# Power.net
KiCad netlist of a schematic drawn in Altium Designer
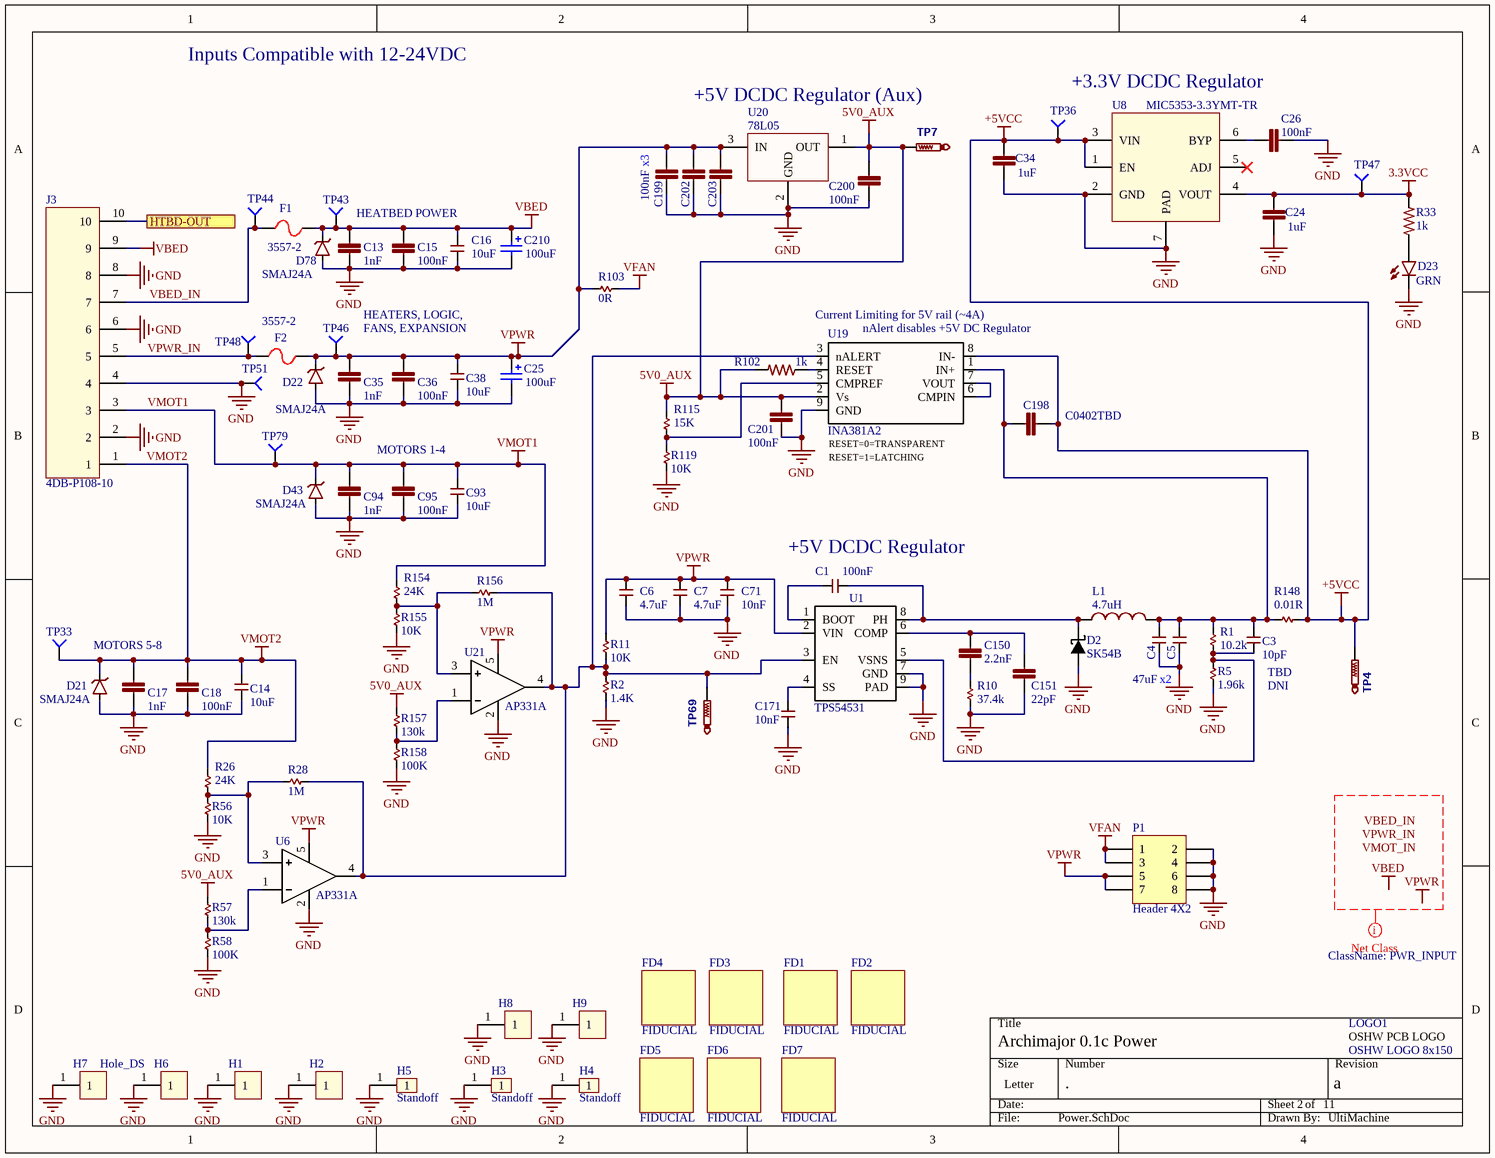
[diagram p0: Power.SchDoc]

(export (version "E")
  (design (tool "Eeschema 10.0.6"))
  (components
    (comp (ref "C1")
      (value "100nF")
      (footprint "C0603")
      (description "CAP CER 0603 100nF 50V 10% X7R")
      (fields (field (name "MANUFACTURER") "Kemet") (field (name "TOLERANCE") "+/- 10%"))
      (libsource (lib "Capacitors") (part "100nF 0603 50V X7R"))
    )
    (comp (ref "C3")
      (value "10pF")
      (footprint "C0402")
      (description "CAP CER 0402 TBD")
      (fields
        (field (name "PART DESCRIPTION") "TBD")
        (field (name "MANUFACTURER") "TBD")
        (field (name "DNI") "DNI")
      )
      (libsource (lib "Capacitors") (part "C0402_TBD"))
    )
    (comp (ref "C4")
      (value "47uF")
      (footprint "C1210")
      (description "CAP CER 47UF 10V X5R 1210")
      (fields (field (name "MANUFACTURER") "Murata") (field (name "TOLERANCE") "10%"))
      (libsource (lib "Capacitors") (part "47uF 1210 10V X5R"))
    )
    (comp (ref "C5")
      (value "47uF")
      (footprint "C1210")
      (description "CAP CER 47UF 10V X5R 1210")
      (fields (field (name "MANUFACTURER") "Murata") (field (name "TOLERANCE") "10%"))
      (libsource (lib "Capacitors") (part "47uF 1210 10V X5R"))
    )
    (comp (ref "C6")
      (value "4.7uF")
      (footprint "C1210")
      (description "CAP CER 4.7UF 50V X7R 1210")
      (fields (field (name "MANUFACTURER") "Murata") (field (name "PART") "4.7uF 1210 50V X7R"))
      (libsource (lib "Capacitors") (part "4.7uF 1210 50V X7R"))
    )
    (comp (ref "C7")
      (value "4.7uF")
      (footprint "C1210")
      (description "CAP CER 4.7UF 50V X7R 1210")
      (fields (field (name "MANUFACTURER") "Murata") (field (name "PART") "4.7uF 1210 50V X7R"))
      (libsource (lib "Capacitors") (part "4.7uF 1210 50V X7R"))
    )
    (comp (ref "C13")
      (value "1nF")
      (footprint "C0402")
      (description "1000pF 50V Ceramic Capacitor X7R 0402 (1005 Metric) 0.039\" L x 0.020\" W (1.00mm x 0.50mm)")
      (fields (field (name "MANUFACTURER") "Murata") (field (name "PART") "1nF 50V X7R 0402"))
      (libsource (lib "3Delight") (part "CAP 1nF 50V 0402 X7R"))
    )
    (comp (ref "C14")
      (value "10uF")
      (footprint "C1206")
      (description "CAP CER 10UF 50V 10% X5R 1206")
      (fields (field (name "MANUFACTURER") "Murata") (field (name "PART") "CAP CER 10UF 50V X5R 1206"))
      (libsource (lib "Capacitors") (part "10uF 1206 50V X5R"))
    )
    (comp (ref "C15")
      (value "100nF")
      (footprint "C0603")
      (description "CAP CER 0603 100nF 50V 10% X7R")
      (fields (field (name "MANUFACTURER") "Kemet") (field (name "PART") "100nF 50V X7R 0603"))
      (libsource (lib "3Delight") (part "C0603C104K5RACTU"))
    )
    (comp (ref "C16")
      (value "10uF")
      (footprint "C1206")
      (description "CAP CER 10UF 50V 10% X5R 1206")
      (fields (field (name "MANUFACTURER") "Murata") (field (name "PART") "CAP CER 10UF 50V X5R 1206"))
      (libsource (lib "Capacitors") (part "10uF 1206 50V X5R"))
    )
    (comp (ref "C17")
      (value "1nF")
      (footprint "C0402")
      (description "1000pF 50V Ceramic Capacitor X7R 0402 (1005 Metric) 0.039\" L x 0.020\" W (1.00mm x 0.50mm)")
      (fields (field (name "MANUFACTURER") "Murata") (field (name "PART") "1nF 50V X7R 0402"))
      (libsource (lib "3Delight") (part "CAP 1nF 50V 0402 X7R"))
    )
    (comp (ref "C18")
      (value "100nF")
      (footprint "C0603")
      (description "CAP CER 0603 100nF 50V 10% X7R")
      (fields (field (name "MANUFACTURER") "Kemet") (field (name "PART") "100nF 50V X7R 0603"))
      (libsource (lib "3Delight") (part "C0603C104K5RACTU"))
    )
    (comp (ref "C24")
      (value "1uF")
      (footprint "C0402")
      (description "CAP CER 0402 1uF 6.3V 10% X5R")
      (fields (field (name "MANUFACTURER") "Murata") (field (name "PART") "1uF 6.3V X5R 0402"))
      (libsource (lib "3Delight") (part "GRM155R60J105KE19D"))
    )
    (comp (ref "C25")
      (value "100uF")
      (footprint "CAP-ELEC-063063077")
      (description "CAP ALUM 100UF 35V 20% SMD")
      (fields (field (name "MANUFACTURER") "Nichicon") (field (name "PART") "100uF 35V SMD Al-El"))
      (libsource (lib "3Delight") (part "UWT1V101MCL1GS"))
    )
    (comp (ref "C26")
      (value "100nF")
      (footprint "C0402")
      (description "CAP CER 0402 100nF 16V 10% X7R")
      (fields (field (name "MANUFACTURER") "Murata") (field (name "PART") "0.1uF 16V X7R 0402"))
      (libsource (lib "") (part "GRM155R71C104KA88D_1"))
    )
    (comp (ref "C34")
      (value "1uF")
      (footprint "C0402")
      (description "CAP CER 0402 1uF 6.3V 10% X5R")
      (fields (field (name "MANUFACTURER") "Murata") (field (name "PART") "1uF 6.3V X5R 0402"))
      (libsource (lib "3Delight") (part "GRM155R60J105KE19D"))
    )
    (comp (ref "C35")
      (value "1nF")
      (footprint "C0402")
      (description "1000pF 50V Ceramic Capacitor X7R 0402 (1005 Metric) 0.039\" L x 0.020\" W (1.00mm x 0.50mm)")
      (fields (field (name "MANUFACTURER") "Murata") (field (name "PART") "1nF 50V X7R 0402"))
      (libsource (lib "3Delight") (part "CAP 1nF 50V 0402 X7R"))
    )
    (comp (ref "C36")
      (value "100nF")
      (footprint "C0603")
      (description "CAP CER 0603 100nF 50V 10% X7R")
      (fields (field (name "MANUFACTURER") "Kemet") (field (name "PART") "100nF 50V X7R 0603"))
      (libsource (lib "3Delight") (part "C0603C104K5RACTU"))
    )
    (comp (ref "C38")
      (value "10uF")
      (footprint "C1206")
      (description "CAP CER 10UF 50V 10% X5R 1206")
      (fields (field (name "MANUFACTURER") "Murata") (field (name "PART") "CAP CER 10UF 50V X5R 1206"))
      (libsource (lib "Capacitors") (part "10uF 1206 50V X5R"))
    )
    (comp (ref "C71")
      (value "10nF")
      (footprint "C0402")
      (description "CAP CER 10nF 50V X7R 0402")
      (fields (field (name "TOLERANCE") "5%") (field (name "MANUFACTURER") "Murata"))
      (libsource (lib "Capacitors") (part "10nF 0402 50V X7R"))
    )
    (comp (ref "C93")
      (value "10uF")
      (footprint "C1206")
      (description "CAP CER 10UF 50V 10% X5R 1206")
      (fields (field (name "MANUFACTURER") "Murata") (field (name "PART") "CAP CER 10UF 50V X5R 1206"))
      (libsource (lib "Capacitors") (part "10uF 1206 50V X5R"))
    )
    (comp (ref "C94")
      (value "1nF")
      (footprint "C0402")
      (description "1000pF 50V Ceramic Capacitor X7R 0402 (1005 Metric) 0.039\" L x 0.020\" W (1.00mm x 0.50mm)")
      (fields (field (name "MANUFACTURER") "Murata") (field (name "PART") "1nF 50V X7R 0402"))
      (libsource (lib "3Delight") (part "CAP 1nF 50V 0402 X7R"))
    )
    (comp (ref "C95")
      (value "100nF")
      (footprint "C0603")
      (description "CAP CER 0603 100nF 50V 10% X7R")
      (fields (field (name "MANUFACTURER") "Kemet") (field (name "PART") "100nF 50V X7R 0603"))
      (libsource (lib "3Delight") (part "C0603C104K5RACTU"))
    )
    (comp (ref "C150")
      (value "2.2nF")
      (footprint "C0402")
      (description "CAP CER 0402 2.2nF 25V C0G")
      (fields (field (name "MANUFACTURER") "Kemet") (field (name "PART") "2.2nF 25V C0G 0402"))
      (libsource (lib "Capacitors") (part "2.2nF 25V C0G 0402"))
    )
    (comp (ref "C151")
      (value "22pF")
      (footprint "C0402")
      (description "CAP CER 0402 22pF 50V 5% C0G")
      (fields (field (name "MANUFACTURER") "AVX") (field (name "PART") "22pF 50V"))
      (libsource (lib "Capacitors") (part "22pF 0402 50V C0G"))
    )
    (comp (ref "C171")
      (value "10nF")
      (footprint "C0402")
      (description "CAP CER 10nF 50V X7R 0402")
      (fields (field (name "TOLERANCE") "5%") (field (name "MANUFACTURER") "Murata"))
      (libsource (lib "Capacitors") (part "10nF 0402 50V X7R"))
    )
    (comp (ref "C198")
      (value "C0402TBD")
      (footprint "C0402")
      (description "Capacitor Non Polarized")
      (libsource (lib "Capacitors") (part "C0402TBD"))
    )
    (comp (ref "C199")
      (value "100nF")
      (footprint "C0603")
      (description "CAP CER 0603 100nF 50V 10% X7R")
      (fields (field (name "MANUFACTURER") "Kemet") (field (name "PART") "100nF 50V X7R 0603"))
      (libsource (lib "3Delight") (part "C0603C104K5RACTU"))
    )
    (comp (ref "C200")
      (value "100nF")
      (footprint "C0402")
      (description "CAP CER 0402 100nF 16V 10% X7R")
      (fields (field (name "MANUFACTURER") "Murata") (field (name "PART") "0.1uF 16V X7R 0402"))
      (libsource (lib "3Delight") (part "GRM155R71C104KA88D"))
    )
    (comp (ref "C201")
      (value "100nF")
      (footprint "C0402")
      (description "CAP CER 0402 100nF 16V 10% X7R")
      (fields (field (name "MANUFACTURER") "Murata") (field (name "PART") "0.1uF 16V X7R 0402"))
      (libsource (lib "3Delight") (part "GRM155R71C104KA88D"))
    )
    (comp (ref "C202")
      (value "100nF")
      (footprint "C0603")
      (description "CAP CER 0603 100nF 50V 10% X7R")
      (fields (field (name "MANUFACTURER") "Kemet") (field (name "PART") "100nF 50V X7R 0603"))
      (libsource (lib "3Delight") (part "C0603C104K5RACTU"))
    )
    (comp (ref "C203")
      (value "100nF")
      (footprint "C0603")
      (description "CAP CER 0603 100nF 50V 10% X7R")
      (fields (field (name "MANUFACTURER") "Kemet") (field (name "PART") "100nF 50V X7R 0603"))
      (libsource (lib "3Delight") (part "C0603C104K5RACTU"))
    )
    (comp (ref "C210")
      (value "100uF")
      (footprint "CAP-ELEC-063063077")
      (description "CAP ALUM 100UF 35V 20% SMD")
      (fields (field (name "MANUFACTURER") "Nichicon") (field (name "PART") "100uF 35V SMD Al-El"))
      (libsource (lib "3Delight") (part "UWT1V101MCL1GS"))
    )
    (comp (ref "D2")
      (value "SK54B")
      (footprint "SMB_DO-214AA_LRG")
      (description "DIODE SCHOTTKY 40V 5A SMB_DO214AA")
      (fields (field (name "MANUFACTURER") "MCC") (field (name "VOLTAGE") "40Vrb"))
      (libsource (lib "Diodes") (part "SK54B"))
    )
    (comp (ref "D21")
      (value "SMAJ24A")
      (footprint "SMA-SM")
      (description "TVS DIODE 24V 38.9V SMA")
      (fields (field (name "MANUFACTURER") "Bourns Inc"))
      (libsource (lib "Diodes") (part "SMAJ24A"))
    )
    (comp (ref "D22")
      (value "SMAJ24A")
      (footprint "SMA-SM")
      (description "TVS DIODE 24V 38.9V SMA")
      (fields (field (name "MANUFACTURER") "Bourns Inc"))
      (libsource (lib "Diodes") (part "SMAJ24A"))
    )
    (comp (ref "D23")
      (value "GRN")
      (footprint "LED2012120")
      (description "LED 0805 Green")
      (fields (field (name "MANUFACTURER") "Dialight") (field (name "PART") "LED GREEN CLEAR 0805 SMD"))
      (libsource (lib "LEDs") (part "5988170107F"))
    )
    (comp (ref "D43")
      (value "SMAJ24A")
      (footprint "SMA-SM")
      (description "TVS DIODE 24V 38.9V SMA")
      (fields (field (name "MANUFACTURER") "Bourns Inc"))
      (libsource (lib "Diodes") (part "SMAJ24A"))
    )
    (comp (ref "D78")
      (value "SMAJ24A")
      (footprint "SMA-SM")
      (description "TVS DIODE 24V 38.9V SMA")
      (fields (field (name "MANUFACTURER") "Bourns Inc"))
      (libsource (lib "Diodes") (part "SMAJ24A"))
    )
    (comp (ref "F1")
      (value "3557-2")
      (footprint "3557")
      (description "FUSE PTH ATO")
      (fields (field (name "MANUFACTURER") "Keystone") (field (name "PART") "Fuse Holder"))
      (libsource (lib "3Delight") (part "3557-2"))
    )
    (comp (ref "F2")
      (value "3557-2")
      (footprint "3557")
      (description "FUSE PTH ATO")
      (fields (field (name "MANUFACTURER") "Keystone") (field (name "PART") "Fuse Holder"))
      (libsource (lib "3Delight") (part "3557-2"))
    )
    (comp (ref "FD1")
      (value "FIDUCIAL")
      (footprint "FIDUCIAL-1X2")
      (libsource (lib "3Delight") (part "FIDUCIAL"))
    )
    (comp (ref "FD2")
      (value "FIDUCIAL")
      (footprint "FIDUCIAL-1X2")
      (libsource (lib "3Delight") (part "FIDUCIAL"))
    )
    (comp (ref "FD3")
      (value "FIDUCIAL")
      (footprint "FIDUCIAL-1X2")
      (libsource (lib "3Delight") (part "FIDUCIAL"))
    )
    (comp (ref "FD4")
      (value "FIDUCIAL")
      (footprint "FIDUCIAL-1X2")
      (libsource (lib "3Delight") (part "FIDUCIAL"))
    )
    (comp (ref "FD5")
      (value "FIDUCIAL")
      (footprint "FIDUCIAL-1X2")
      (libsource (lib "3Delight") (part "FIDUCIAL"))
    )
    (comp (ref "FD6")
      (value "FIDUCIAL")
      (footprint "FIDUCIAL-1X2")
      (libsource (lib "3Delight") (part "FIDUCIAL"))
    )
    (comp (ref "FD7")
      (value "FIDUCIAL")
      (footprint "FIDUCIAL-1X2")
      (libsource (lib "3Delight") (part "FIDUCIAL"))
    )
    (comp (ref "H1")
      (value "Hole_DS")
      (footprint "Wave_hole_3x7-doubleSided")
      (libsource (lib "Archim_0.4") (part "Hole_DS"))
    )
    (comp (ref "H2")
      (value "Hole_DS")
      (footprint "Wave_hole_3x7-doubleSided")
      (libsource (lib "Archim_0.4") (part "Hole_DS"))
    )
    (comp (ref "H3")
      (value "Standoff")
      (footprint "Standoff3mmTopConn")
      (description "Mechanical - Top connect")
      (libsource (lib "3Delight") (part "Standoff3TopConn"))
    )
    (comp (ref "H4")
      (value "Standoff")
      (footprint "Standoff3mmTopConn")
      (description "Mechanical - Top connect")
      (libsource (lib "3Delight") (part "Standoff3TopConn"))
    )
    (comp (ref "H5")
      (value "Standoff")
      (footprint "Standoff3mmTopConn")
      (description "Mechanical - Top connect")
      (libsource (lib "3Delight") (part "Standoff3TopConn"))
    )
    (comp (ref "H6")
      (value "Hole_DS")
      (footprint "Wave_hole_3x7-doubleSided")
      (libsource (lib "Archim_0.4") (part "Hole_DS"))
    )
    (comp (ref "H7")
      (value "Hole_DS")
      (footprint "Wave_hole_3x7-doubleSided")
      (libsource (lib "Archim_0.4") (part "Hole_DS"))
    )
    (comp (ref "H8")
      (value "Hole_DS")
      (footprint "Wave_hole_3x7-doubleSided")
      (libsource (lib "Archim_0.4") (part "Hole_DS"))
    )
    (comp (ref "H9")
      (value "Hole_DS")
      (footprint "Wave_hole_3x7-doubleSided")
      (libsource (lib "Archim_0.4") (part "Hole_DS"))
    )
    (comp (ref "J3")
      (value "4DB-P108-10")
      (footprint "CON-Barrier-10-8.26mm")
      (description "CONN BARRIER STRIP 10CIRC 0.325\"")
      (fields (field (name "MANUFACTURER") "TE") (field (name "TOLERANCE") "NA"))
      (libsource (lib "Connectors") (part "10 Pos barrier"))
    )
    (comp (ref "L1")
      (value "4.7uH")
      (footprint "IND_10X10")
      (description "FIXED IND 4.7UH 10A 15.5 MOHM")
      (fields (field (name "MANUFACTURER") "Bourns") (field (name "PART") "4.7uH 10A"))
      (libsource (lib "Inductors") (part "4.7uH 10A"))
    )
    (comp (ref "LOGO1")
      (value "OSHW LOGO 8x150")
      (footprint "OSHW_8X150_NOTEXT")
      (libsource (lib "MISC") (part "OSHW LOGO 8x150"))
    )
    (comp (ref "P1")
      (value "Header 4X2")
      (footprint "HDR2X4")
      (description "Header, 4-Pin, Dual row")
      (fields (field (name "MANUFACTURER") "Multicomp") (field (name "PART") "CONN 8Pin 2Row 0.1\""))
      (libsource (lib "Miscellaneous Connectors") (part "Header 4X2"))
    )
    (comp (ref "R1")
      (value "10.2k")
      (footprint "R0402")
      (description "RES SMD 10.2K OHM 1% 1/16W 0402")
      (fields (field (name "MANUFACTURER") "Yageo") (field (name "PART") "10.2k 1% 0402"))
      (libsource (lib "Resistors") (part "10.2k 1% 0402"))
    )
    (comp (ref "R2")
      (value "1.4K")
      (footprint "R0402")
      (description "RES SMD 1.4K OHM 1% 1/16W 0402")
      (fields (field (name "MANUFACTURER") "Stackpole") (field (name "TOLERANCE") "+/- 1%"))
      (libsource (lib "Resistors") (part "1.4k 1% 0402"))
    )
    (comp (ref "R5")
      (value "1.96k")
      (footprint "R0402")
      (description "RES SMD 1.96K OHM 1% 1/16W 0402")
      (fields (field (name "MANUFACTURER") "Yageo") (field (name "PART") "1.96k 1% 0402"))
      (libsource (lib "Resistors") (part "1.96k 1% 0402"))
    )
    (comp (ref "R10")
      (value "37.4k")
      (footprint "R0402")
      (description "RES SMD 37.4K OHM 1% 1/16W 0402")
      (fields (field (name "MANUFACTURER") "Yageo") (field (name "TOLERANCE") "1%"))
      (libsource (lib "Resistors") (part "37.4K 1% 0402"))
    )
    (comp (ref "R11")
      (value "10K")
      (footprint "R0402")
      (description "RES SMD 10K OHM 1% 1/16W 0402")
      (fields (field (name "MANUFACTURER") "Yageo") (field (name "PART") "10k 1% 0402"))
      (libsource (lib "Resistors") (part "10k 1% 0402"))
    )
    (comp (ref "R26")
      (value "24K")
      (footprint "R0402")
      (description "RES SMD 24K OHM 1% 1/16W 0402")
      (fields (field (name "MANUFACTURER") "Visha Dale") (field (name "TOLERANCE") "+/- 1%"))
      (libsource (lib "Resistors") (part "24k 1% 0402"))
    )
    (comp (ref "R28")
      (value "1M")
      (footprint "Passives:R0402")
      (description "RES 0402 1M 100mW 5%")
      (fields (field (name "MANUFACTURER") "Panasonic") (field (name "PART") "1M 5% 0402"))
      (libsource (lib "Resistors") (part "1M 5% 0402"))
    )
    (comp (ref "R33")
      (value "1k")
      (footprint "R0402")
      (description "RES 0402 1k 63mW 1%")
      (fields (field (name "MANUFACTURER") "Yageo") (field (name "PART") "1k 1% 0402"))
      (libsource (lib "3Delight") (part "RK73H1ETTP1001F"))
    )
    (comp (ref "R56")
      (value "10K")
      (footprint "R0402")
      (description "RES SMD 10K OHM 1% 1/16W 0402")
      (fields (field (name "MANUFACTURER") "Yageo") (field (name "PART") "10k 1% 0402"))
      (libsource (lib "Resistors") (part "10k 1% 0402"))
    )
    (comp (ref "R57")
      (value "130k")
      (footprint "Passives:R0402")
      (description "RES SMD 130K OHM 5% 1/16W 0402")
      (fields (field (name "MANUFACTURER") "Yageo") (field (name "PART") "130k 1% 0402"))
      (libsource (lib "Resistors") (part "130k 1% 0402"))
    )
    (comp (ref "R58")
      (value "100K")
      (footprint "Passives:R0402")
      (description "RES SMD 100K OHM 1% 1/16W 0402")
      (fields (field (name "MANUFACTURER") "Samsung") (field (name "PART") "100k 1% 0402"))
      (libsource (lib "Resistors") (part "100k 1% 0402"))
    )
    (comp (ref "R102")
      (value "1k")
      (footprint "R0402")
      (description "RES 0402 1k 63mW 1%")
      (fields (field (name "MANUFACTURER") "Yageo") (field (name "PART") "1k 1% 0402"))
      (libsource (lib "3Delight") (part "RK73H1ETTP1001F"))
    )
    (comp (ref "R103")
      (value "0R")
      (footprint "R0603")
      (description "RES SMD 0.0OHM JUMPER 1/10W 0603")
      (fields (field (name "MANUFACTURER") "Bourns") (field (name "TOLERANCE") "-NA-"))
      (libsource (lib "Resistors") (part "0R 0603"))
    )
    (comp (ref "R115")
      (value "15K")
      (footprint "R0402")
      (description "RES SMD 15K 1% 1/16W 0402")
      (fields (field (name "MANUFACTURER") "Samsung") (field (name "PART") "15K 1% 0402"))
      (libsource (lib "Resistors") (part "15K 1% 0402"))
    )
    (comp (ref "R119")
      (value "10K")
      (footprint "R0402")
      (description "RES SMD 10K OHM 1% 1/16W 0402")
      (fields (field (name "MANUFACTURER") "Yageo") (field (name "PART") "10k 1% 0402"))
      (libsource (lib "Resistors") (part "10k 1% 0402"))
    )
    (comp (ref "R148")
      (value "0.01R")
      (footprint "R0805")
      (description "RES 0.01 OHM 1% 1/2W 0805")
      (fields (field (name "MANUFACTURER") "Susumu") (field (name "PART") "0.01 1% 0.5W 0805"))
      (libsource (lib "Resistors") (part "0.01R 1% 0805"))
    )
    (comp (ref "R154")
      (value "24K")
      (footprint "R0402")
      (description "RES SMD 24K OHM 1% 1/16W 0402")
      (fields (field (name "MANUFACTURER") "Visha Dale") (field (name "TOLERANCE") "+/- 1%"))
      (libsource (lib "Resistors") (part "24k 1% 0402"))
    )
    (comp (ref "R155")
      (value "10K")
      (footprint "R0402")
      (description "RES SMD 10K OHM 1% 1/16W 0402")
      (fields (field (name "MANUFACTURER") "Yageo") (field (name "PART") "10k 1% 0402"))
      (libsource (lib "Resistors") (part "10k 1% 0402"))
    )
    (comp (ref "R156")
      (value "1M")
      (footprint "Passives:R0402")
      (description "RES 0402 1M 100mW 5%")
      (fields (field (name "MANUFACTURER") "Panasonic") (field (name "PART") "1M 5% 0402"))
      (libsource (lib "Resistors") (part "1M 5% 0402"))
    )
    (comp (ref "R157")
      (value "130k")
      (footprint "Passives:R0402")
      (description "RES SMD 130K OHM 5% 1/16W 0402")
      (fields (field (name "MANUFACTURER") "Yageo") (field (name "PART") "130k 1% 0402"))
      (libsource (lib "Resistors") (part "130k 1% 0402"))
    )
    (comp (ref "R158")
      (value "100K")
      (footprint "Passives:R0402")
      (description "RES SMD 100K OHM 1% 1/16W 0402")
      (fields (field (name "MANUFACTURER") "Samsung") (field (name "PART") "100k 1% 0402"))
      (libsource (lib "Resistors") (part "100k 1% 0402"))
    )
    (comp (ref "TP4")
      (value "TestPoint")
      (footprint "TP1-27")
      (description "Test Point")
      (libsource (lib "3Delight") (part "TestPoint"))
    )
    (comp (ref "TP7")
      (value "TestPoint")
      (footprint "TP1-27")
      (description "Test Point")
      (libsource (lib "") (part "TestPoint_1"))
    )
    (comp (ref "TP33")
      (value "TP4")
      (footprint "TP-2")
      (description "Socket")
      (libsource (lib "Archim") (part "Socket"))
    )
    (comp (ref "TP36")
      (value "TP4")
      (footprint "TP-2")
      (description "Socket")
      (libsource (lib "Archim") (part "Socket"))
    )
    (comp (ref "TP43")
      (value "TP4")
      (footprint "TP-2")
      (description "Socket")
      (libsource (lib "Archim") (part "Socket"))
    )
    (comp (ref "TP44")
      (value "TP4")
      (footprint "TP-2")
      (description "Socket")
      (libsource (lib "Archim") (part "Socket"))
    )
    (comp (ref "TP46")
      (value "TP4")
      (footprint "TP-2")
      (description "Socket")
      (libsource (lib "Archim") (part "Socket"))
    )
    (comp (ref "TP47")
      (value "TP4")
      (footprint "TP-2")
      (description "Socket")
      (libsource (lib "Archim") (part "Socket"))
    )
    (comp (ref "TP48")
      (value "TP4")
      (footprint "TP-2")
      (description "Socket")
      (libsource (lib "Archim") (part "Socket"))
    )
    (comp (ref "TP51")
      (value "TP4")
      (footprint "TP-2")
      (description "Socket")
      (libsource (lib "Archim") (part "Socket"))
    )
    (comp (ref "TP69")
      (value "TestPoint")
      (footprint "TP1-27")
      (description "Test Point")
      (libsource (lib "3Delight") (part "TestPoint"))
    )
    (comp (ref "TP79")
      (value "TP4")
      (footprint "TP-2")
      (description "Socket")
      (libsource (lib "Archim") (part "Socket"))
    )
    (comp (ref "U1")
      (value "TPS54531")
      (footprint "SOIC127P600X170_HS-9L")
      (description "IC REG BUCK ADJ 5A 8SOPWRPAD")
      (fields (field (name "MANUFACTURER") "TI"))
      (libsource (lib "ICs-Power") (part "TPS54531"))
    )
    (comp (ref "U6")
      (value "AP331A")
      (footprint "SOT23-5")
      (description "IC QUAD DIFF COMPARATOR 14 -SOIC")
      (fields (field (name "MANUFACTURER") "TEXAS INSTRUMENTS"))
      (libsource (lib "ICs-Analog") (part "AP331A"))
    )
    (comp (ref "U8")
      (value "MIC5353-3.3YMT-TR")
      (footprint "TDFN1616-6LD-PL-1")
      (description "LDO 3.3V 500mA - low ESR Cout")
      (fields (field (name "MANUFACTURER") "Microchip") (field (name "PART") "IC REG LDO 3.3V 0.5A 6TMLF"))
      (libsource (lib "Tigershark3D") (part "MIC5353-3.3YMT-TR"))
    )
    (comp (ref "U19")
      (value "INA381A2")
      (footprint "WSON8_2x2mm")
      (description "IC COMPARATOR BIDIR 8WSON")
      (fields (field (name "MANUFACTURER") "TI") (field (name "TOLERANCE") "-NA-"))
      (libsource (lib "ICs-Analog") (part "INA381_ALT"))
    )
    (comp (ref "U20")
      (value "78L05")
      (footprint "SOT-89-3")
      (description "IC REG LINEAR 5V 100MA SOT89-3")
      (fields (field (name "MANUFACTURER") "ST") (field (name "TOLERANCE") "-NA-"))
      (libsource (lib "ICs-Power") (part "78L05"))
    )
    (comp (ref "U21")
      (value "AP331A")
      (footprint "SOT23-5")
      (description "IC QUAD DIFF COMPARATOR 14 -SOIC")
      (fields (field (name "MANUFACTURER") "TEXAS INSTRUMENTS"))
      (libsource (lib "ICs-Analog") (part "AP331A"))
    )
  )
  (nets
    (net (code "1") (name "+5VCC") (class "Default")
      (node (ref "C198") (pin "1") (pinfunction "1_1") (pintype "passive"))
      (node (ref "C34") (pin "1") (pinfunction "1_1") (pintype "passive"))
      (node (ref "R148") (pin "2") (pinfunction "2_2") (pintype "passive"))
      (node (ref "TP36") (pin "1") (pinfunction "1_1") (pintype "passive"))
      (node (ref "TP4") (pin "TP") (pinfunction "TP_TP") (pintype "passive"))
      (node (ref "U19") (pin "8") (pinfunction "IN-_8") (pintype "power_in"))
      (node (ref "U8") (pin "1") (pinfunction "EN_1") (pintype "power_in"))
      (node (ref "U8") (pin "3") (pinfunction "VIN_3") (pintype "power_in"))
    )
    (net (code "2") (name "/HTBD-OUT") (class "Default")
      (node (ref "J3") (pin "10") (pinfunction "10_10") (pintype "passive"))
    )
    (net (code "3") (name "/VBED_IN") (class "Default")
      (node (ref "F1") (pin "1") (pinfunction "1_1") (pintype "passive"))
      (node (ref "J3") (pin "7") (pinfunction "7_7") (pintype "passive"))
      (node (ref "TP44") (pin "1") (pinfunction "1_1") (pintype "passive"))
    )
    (net (code "5") (name "/VPWR_IN") (class "Default")
      (node (ref "F2") (pin "1") (pinfunction "1_1") (pintype "passive"))
      (node (ref "J3") (pin "5") (pinfunction "5_5") (pintype "passive"))
      (node (ref "TP48") (pin "1") (pinfunction "1_1") (pintype "passive"))
    )
    (net (code "6") (name "3.3VCC") (class "Default")
      (node (ref "C24") (pin "1") (pinfunction "1_1") (pintype "passive"))
      (node (ref "R33") (pin "2") (pinfunction "2_2") (pintype "passive"))
      (node (ref "TP47") (pin "1") (pinfunction "1_1") (pintype "passive"))
      (node (ref "U8") (pin "4") (pinfunction "VOUT_4") (pintype "power_in"))
    )
    (net (code "7") (name "5V0_AUX") (class "Default")
      (node (ref "C200") (pin "2") (pinfunction "2_2") (pintype "passive"))
      (node (ref "C201") (pin "2") (pinfunction "2_2") (pintype "passive"))
      (node (ref "R102") (pin "2") (pinfunction "2_2") (pintype "passive"))
      (node (ref "R115") (pin "2") (pinfunction "2_2") (pintype "passive"))
      (node (ref "R157") (pin "2") (pinfunction "2_2") (pintype "passive"))
      (node (ref "R57") (pin "2") (pinfunction "2_2") (pintype "passive"))
      (node (ref "TP7") (pin "TP") (pinfunction "TP_TP") (pintype "passive"))
      (node (ref "U19") (pin "2") (pinfunction "Vs_2") (pintype "power_in"))
      (node (ref "U20") (pin "1") (pinfunction "OUT_1") (pintype "power_in"))
    )
    (net (code "8") (name "GND") (class "Default")
      (node (ref "C13") (pin "2") (pinfunction "2_2") (pintype "passive"))
      (node (ref "C14") (pin "1") (pinfunction "1_1") (pintype "passive"))
      (node (ref "C15") (pin "2") (pinfunction "2_2") (pintype "passive"))
      (node (ref "C151") (pin "1") (pinfunction "1_1") (pintype "passive"))
      (node (ref "C16") (pin "1") (pinfunction "1_1") (pintype "passive"))
      (node (ref "C17") (pin "2") (pinfunction "2_2") (pintype "passive"))
      (node (ref "C171") (pin "1") (pinfunction "1_1") (pintype "passive"))
      (node (ref "C18") (pin "2") (pinfunction "2_2") (pintype "passive"))
      (node (ref "C199") (pin "2") (pinfunction "2_2") (pintype "passive"))
      (node (ref "C200") (pin "1") (pinfunction "1_1") (pintype "passive"))
      (node (ref "C201") (pin "1") (pinfunction "1_1") (pintype "passive"))
      (node (ref "C202") (pin "2") (pinfunction "2_2") (pintype "passive"))
      (node (ref "C203") (pin "2") (pinfunction "2_2") (pintype "passive"))
      (node (ref "C210") (pin "2") (pinfunction "2_2") (pintype "passive"))
      (node (ref "C24") (pin "2") (pinfunction "2_2") (pintype "passive"))
      (node (ref "C25") (pin "2") (pinfunction "2_2") (pintype "passive"))
      (node (ref "C26") (pin "2") (pinfunction "2_2") (pintype "passive"))
      (node (ref "C34") (pin "2") (pinfunction "2_2") (pintype "passive"))
      (node (ref "C35") (pin "2") (pinfunction "2_2") (pintype "passive"))
      (node (ref "C36") (pin "2") (pinfunction "2_2") (pintype "passive"))
      (node (ref "C38") (pin "1") (pinfunction "1_1") (pintype "passive"))
      (node (ref "C4") (pin "1") (pinfunction "1_1") (pintype "passive"))
      (node (ref "C5") (pin "1") (pinfunction "1_1") (pintype "passive"))
      (node (ref "C6") (pin "1") (pinfunction "1_1") (pintype "passive"))
      (node (ref "C7") (pin "1") (pinfunction "1_1") (pintype "passive"))
      (node (ref "C71") (pin "1") (pinfunction "1_1") (pintype "passive"))
      (node (ref "C93") (pin "1") (pinfunction "1_1") (pintype "passive"))
      (node (ref "C94") (pin "2") (pinfunction "2_2") (pintype "passive"))
      (node (ref "C95") (pin "2") (pinfunction "2_2") (pintype "passive"))
      (node (ref "D2") (pin "A") (pinfunction "ANODE_A") (pintype "passive"))
      (node (ref "D21") (pin "A") (pinfunction "A_A") (pintype "passive"))
      (node (ref "D22") (pin "A") (pinfunction "A_A") (pintype "passive"))
      (node (ref "D23") (pin "C") (pinfunction "C_C") (pintype "passive"))
      (node (ref "D43") (pin "A") (pinfunction "A_A") (pintype "passive"))
      (node (ref "D78") (pin "A") (pinfunction "A_A") (pintype "passive"))
      (node (ref "H1") (pin "1") (pinfunction "1_1") (pintype "power_in"))
      (node (ref "H2") (pin "1") (pinfunction "1_1") (pintype "power_in"))
      (node (ref "H3") (pin "1") (pinfunction "1_1") (pintype "power_in"))
      (node (ref "H4") (pin "1") (pinfunction "1_1") (pintype "power_in"))
      (node (ref "H5") (pin "1") (pinfunction "1_1") (pintype "power_in"))
      (node (ref "H6") (pin "1") (pinfunction "1_1") (pintype "power_in"))
      (node (ref "H7") (pin "1") (pinfunction "1_1") (pintype "power_in"))
      (node (ref "H8") (pin "1") (pinfunction "1_1") (pintype "power_in"))
      (node (ref "H9") (pin "1") (pinfunction "1_1") (pintype "power_in"))
      (node (ref "J3") (pin "2") (pinfunction "2_2") (pintype "passive"))
      (node (ref "J3") (pin "4") (pinfunction "4_4") (pintype "passive"))
      (node (ref "J3") (pin "6") (pinfunction "6_6") (pintype "passive"))
      (node (ref "J3") (pin "8") (pinfunction "8_8") (pintype "passive"))
      (node (ref "P1") (pin "2") (pinfunction "2_2") (pintype "passive"))
      (node (ref "P1") (pin "4") (pinfunction "4_4") (pintype "passive"))
      (node (ref "P1") (pin "6") (pinfunction "6_6") (pintype "passive"))
      (node (ref "P1") (pin "8") (pinfunction "8_8") (pintype "passive"))
      (node (ref "R10") (pin "1") (pinfunction "1_1") (pintype "passive"))
      (node (ref "R119") (pin "1") (pinfunction "1_1") (pintype "passive"))
      (node (ref "R155") (pin "1") (pinfunction "1_1") (pintype "passive"))
      (node (ref "R158") (pin "1") (pinfunction "1_1") (pintype "passive"))
      (node (ref "R2") (pin "1") (pinfunction "1_1") (pintype "passive"))
      (node (ref "R5") (pin "1") (pinfunction "1_1") (pintype "passive"))
      (node (ref "R56") (pin "1") (pinfunction "1_1") (pintype "passive"))
      (node (ref "R58") (pin "1") (pinfunction "1_1") (pintype "passive"))
      (node (ref "TP51") (pin "1") (pinfunction "1_1") (pintype "passive"))
      (node (ref "U1") (pin "7") (pinfunction "GND_7") (pintype "passive"))
      (node (ref "U1") (pin "9") (pinfunction "PAD_9") (pintype "passive"))
      (node (ref "U19") (pin "9") (pinfunction "GND_9") (pintype "power_in"))
      (node (ref "U20") (pin "2") (pinfunction "GND_2") (pintype "power_in"))
      (node (ref "U21") (pin "2") (pinfunction "GND_2") (pintype "power_in"))
      (node (ref "U6") (pin "2") (pinfunction "GND_2") (pintype "power_in"))
      (node (ref "U8") (pin "2") (pinfunction "GND_2") (pintype "power_in"))
      (node (ref "U8") (pin "7") (pinfunction "PAD_7") (pintype "power_in"))
    )
    (net (code "9") (name "Net-(C150-Pad1)") (class "Default")
      (node (ref "C150") (pin "1") (pinfunction "1_1") (pintype "passive"))
      (node (ref "R10") (pin "2") (pinfunction "2_2") (pintype "passive"))
    )
    (net (code "10") (name "Net-(D2-CATHODE)") (class "Default")
      (node (ref "C1") (pin "2") (pinfunction "2_2") (pintype "passive"))
      (node (ref "D2") (pin "K") (pinfunction "CATHODE_K") (pintype "passive"))
      (node (ref "L1") (pin "1") (pinfunction "1_1") (pintype "passive"))
      (node (ref "U1") (pin "8") (pinfunction "PH_8") (pintype "passive"))
    )
    (net (code "11") (name "Net-(D23-PadA)") (class "Default")
      (node (ref "D23") (pin "A") (pinfunction "A_A") (pintype "passive"))
      (node (ref "R33") (pin "1") (pinfunction "1_1") (pintype "passive"))
    )
    (net (code "12") (name "Net-(U1-BOOT)") (class "Default")
      (node (ref "C1") (pin "1") (pinfunction "1_1") (pintype "passive"))
      (node (ref "U1") (pin "1") (pinfunction "BOOT_1") (pintype "passive"))
    )
    (net (code "13") (name "Net-(U1-COMP)") (class "Default")
      (node (ref "C150") (pin "2") (pinfunction "2_2") (pintype "passive"))
      (node (ref "C151") (pin "2") (pinfunction "2_2") (pintype "passive"))
      (node (ref "U1") (pin "6") (pinfunction "COMP_6") (pintype "passive"))
    )
    (net (code "14") (name "Net-(U1-EN)") (class "Default")
      (node (ref "R11") (pin "1") (pinfunction "1_1") (pintype "passive"))
      (node (ref "R156") (pin "1") (pinfunction "1_1") (pintype "passive"))
      (node (ref "R2") (pin "2") (pinfunction "2_2") (pintype "passive"))
      (node (ref "R28") (pin "1") (pinfunction "1_1") (pintype "passive"))
      (node (ref "TP69") (pin "TP") (pinfunction "TP_TP") (pintype "passive"))
      (node (ref "U1") (pin "3") (pinfunction "EN_3") (pintype "passive"))
      (node (ref "U19") (pin "3") (pinfunction "nALERT_3") (pintype "power_in"))
      (node (ref "U21") (pin "4") (pinfunction "OUT_4") (pintype "passive"))
      (node (ref "U6") (pin "4") (pinfunction "OUT_4") (pintype "passive"))
    )
    (net (code "15") (name "Net-(U1-SS)") (class "Default")
      (node (ref "C171") (pin "2") (pinfunction "2_2") (pintype "passive"))
      (node (ref "U1") (pin "4") (pinfunction "SS_4") (pintype "passive"))
    )
    (net (code "16") (name "Net-(U1-VSNS)") (class "Default")
      (node (ref "C3") (pin "1") (pinfunction "1_1") (pintype "passive"))
      (node (ref "R1") (pin "2") (pinfunction "2_2") (pintype "passive"))
      (node (ref "R5") (pin "2") (pinfunction "2_2") (pintype "passive"))
      (node (ref "U1") (pin "5") (pinfunction "VSNS_5") (pintype "passive"))
    )
    (net (code "17") (name "Net-(U6-IN+)") (class "Default")
      (node (ref "R26") (pin "2") (pinfunction "2_2") (pintype "passive"))
      (node (ref "R28") (pin "2") (pinfunction "2_2") (pintype "passive"))
      (node (ref "R56") (pin "2") (pinfunction "2_2") (pintype "passive"))
      (node (ref "U6") (pin "3") (pinfunction "IN+_3") (pintype "passive"))
    )
    (net (code "18") (name "Net-(U6-IN-)") (class "Default")
      (node (ref "R57") (pin "1") (pinfunction "1_1") (pintype "passive"))
      (node (ref "R58") (pin "2") (pinfunction "2_2") (pintype "passive"))
      (node (ref "U6") (pin "1") (pinfunction "IN-_1") (pintype "passive"))
    )
    (net (code "19") (name "Net-(U8-BYP)") (class "Default")
      (node (ref "C26") (pin "1") (pinfunction "1_1") (pintype "passive"))
      (node (ref "U8") (pin "6") (pinfunction "BYP_6") (pintype "power_in"))
    )
    (net (code "20") (name "Net-(U19-CMPIN)") (class "Default")
      (node (ref "U19") (pin "6") (pinfunction "CMPIN_6") (pintype "power_in"))
      (node (ref "U19") (pin "7") (pinfunction "VOUT_7") (pintype "power_in"))
    )
    (net (code "21") (name "Net-(U19-CMPREF)") (class "Default")
      (node (ref "R115") (pin "1") (pinfunction "1_1") (pintype "passive"))
      (node (ref "R119") (pin "2") (pinfunction "2_2") (pintype "passive"))
      (node (ref "U19") (pin "5") (pinfunction "CMPREF_5") (pintype "power_in"))
    )
    (net (code "22") (name "Net-(U19-IN+)") (class "Default")
      (node (ref "C198") (pin "2") (pinfunction "2_2") (pintype "passive"))
      (node (ref "C3") (pin "2") (pinfunction "2_2") (pintype "passive"))
      (node (ref "C4") (pin "2") (pinfunction "2_2") (pintype "passive"))
      (node (ref "C5") (pin "2") (pinfunction "2_2") (pintype "passive"))
      (node (ref "L1") (pin "2") (pinfunction "2_2") (pintype "passive"))
      (node (ref "R1") (pin "1") (pinfunction "1_1") (pintype "passive"))
      (node (ref "R148") (pin "1") (pinfunction "1_1") (pintype "passive"))
      (node (ref "U19") (pin "1") (pinfunction "IN+_1") (pintype "power_in"))
    )
    (net (code "23") (name "Net-(U19-RESET)") (class "Default")
      (node (ref "R102") (pin "1") (pinfunction "1_1") (pintype "passive"))
      (node (ref "U19") (pin "4") (pinfunction "RESET_4") (pintype "power_in"))
    )
    (net (code "24") (name "Net-(U21-IN+)") (class "Default")
      (node (ref "R154") (pin "2") (pinfunction "2_2") (pintype "passive"))
      (node (ref "R155") (pin "2") (pinfunction "2_2") (pintype "passive"))
      (node (ref "R156") (pin "2") (pinfunction "2_2") (pintype "passive"))
      (node (ref "U21") (pin "3") (pinfunction "IN+_3") (pintype "passive"))
    )
    (net (code "25") (name "Net-(U21-IN-)") (class "Default")
      (node (ref "R157") (pin "1") (pinfunction "1_1") (pintype "passive"))
      (node (ref "R158") (pin "2") (pinfunction "2_2") (pintype "passive"))
      (node (ref "U21") (pin "1") (pinfunction "IN-_1") (pintype "passive"))
    )
    (net (code "26") (name "VBED") (class "Default")
      (node (ref "C13") (pin "1") (pinfunction "1_1") (pintype "passive"))
      (node (ref "C15") (pin "1") (pinfunction "1_1") (pintype "passive"))
      (node (ref "C16") (pin "2") (pinfunction "2_2") (pintype "passive"))
      (node (ref "C210") (pin "1") (pinfunction "1_1") (pintype "passive"))
      (node (ref "D78") (pin "K") (pinfunction "K_K") (pintype "passive"))
      (node (ref "F1") (pin "2") (pinfunction "2_2") (pintype "passive"))
      (node (ref "J3") (pin "9") (pinfunction "9_9") (pintype "passive"))
      (node (ref "TP43") (pin "1") (pinfunction "1_1") (pintype "passive"))
    )
    (net (code "27") (name "VFAN") (class "Default")
      (node (ref "P1") (pin "1") (pinfunction "1_1") (pintype "passive"))
      (node (ref "P1") (pin "3") (pinfunction "3_3") (pintype "passive"))
      (node (ref "R103") (pin "2") (pinfunction "2_2") (pintype "passive"))
    )
    (net (code "28") (name "VMOT1") (class "Default")
      (node (ref "C93") (pin "2") (pinfunction "2_2") (pintype "passive"))
      (node (ref "C94") (pin "1") (pinfunction "1_1") (pintype "passive"))
      (node (ref "C95") (pin "1") (pinfunction "1_1") (pintype "passive"))
      (node (ref "D43") (pin "K") (pinfunction "K_K") (pintype "passive"))
      (node (ref "J3") (pin "3") (pinfunction "3_3") (pintype "passive"))
      (node (ref "R154") (pin "1") (pinfunction "1_1") (pintype "passive"))
      (node (ref "TP79") (pin "1") (pinfunction "1_1") (pintype "passive"))
    )
    (net (code "29") (name "VMOT2") (class "Default")
      (node (ref "C14") (pin "2") (pinfunction "2_2") (pintype "passive"))
      (node (ref "C17") (pin "1") (pinfunction "1_1") (pintype "passive"))
      (node (ref "C18") (pin "1") (pinfunction "1_1") (pintype "passive"))
      (node (ref "D21") (pin "K") (pinfunction "K_K") (pintype "passive"))
      (node (ref "J3") (pin "1") (pinfunction "1_1") (pintype "passive"))
      (node (ref "R26") (pin "1") (pinfunction "1_1") (pintype "passive"))
      (node (ref "TP33") (pin "1") (pinfunction "1_1") (pintype "passive"))
    )
    (net (code "30") (name "VPWR") (class "Default")
      (node (ref "C199") (pin "1") (pinfunction "1_1") (pintype "passive"))
      (node (ref "C202") (pin "1") (pinfunction "1_1") (pintype "passive"))
      (node (ref "C203") (pin "1") (pinfunction "1_1") (pintype "passive"))
      (node (ref "C25") (pin "1") (pinfunction "1_1") (pintype "passive"))
      (node (ref "C35") (pin "1") (pinfunction "1_1") (pintype "passive"))
      (node (ref "C36") (pin "1") (pinfunction "1_1") (pintype "passive"))
      (node (ref "C38") (pin "2") (pinfunction "2_2") (pintype "passive"))
      (node (ref "C6") (pin "2") (pinfunction "2_2") (pintype "passive"))
      (node (ref "C7") (pin "2") (pinfunction "2_2") (pintype "passive"))
      (node (ref "C71") (pin "2") (pinfunction "2_2") (pintype "passive"))
      (node (ref "D22") (pin "K") (pinfunction "K_K") (pintype "passive"))
      (node (ref "F2") (pin "2") (pinfunction "2_2") (pintype "passive"))
      (node (ref "P1") (pin "5") (pinfunction "5_5") (pintype "passive"))
      (node (ref "P1") (pin "7") (pinfunction "7_7") (pintype "passive"))
      (node (ref "R103") (pin "1") (pinfunction "1_1") (pintype "passive"))
      (node (ref "R11") (pin "2") (pinfunction "2_2") (pintype "passive"))
      (node (ref "TP46") (pin "1") (pinfunction "1_1") (pintype "passive"))
      (node (ref "U1") (pin "2") (pinfunction "VIN_2") (pintype "passive"))
      (node (ref "U20") (pin "3") (pinfunction "IN_3") (pintype "power_in"))
      (node (ref "U21") (pin "5") (pinfunction "VCC_5") (pintype "power_in"))
      (node (ref "U6") (pin "5") (pinfunction "VCC_5") (pintype "power_in"))
    )
    (net (code "31") (name "unconnected-(U8-ADJ-Pad5)") (class "Default")
      (node (ref "U8") (pin "5") (pinfunction "ADJ_5") (pintype "power_in+no_connect"))
    )
  )
)
